# duck-v2.net
KiCad netlist of a schematic drawn in EAGLE
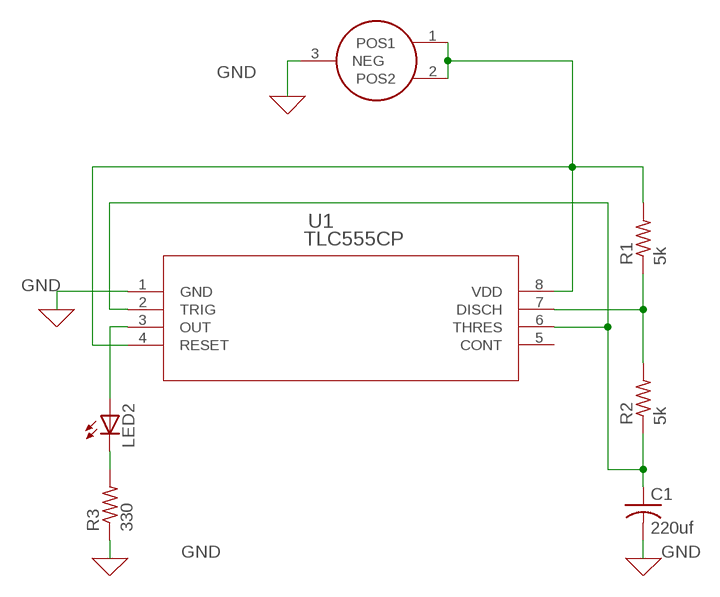
[diagram p0: schematic, sheet 1]

(export (version "E")
  (design (tool "Eeschema 10.0.6"))
  (components
    (comp (ref "C1")
      (value "220uf")
      (footprint "eagle-import:C025-024X044")
      (libsource (lib "eagle-import") (part "C-US025-024X044"))
    )
    (comp (ref "LED2")
      (value "LED5MM")
      (footprint "eagle-import:LED5MM")
      (libsource (lib "eagle-import") (part "LED5MM"))
    )
    (comp (ref "R1")
      (value "5k")
      (footprint "eagle-import:0204_7")
      (libsource (lib "eagle-import") (part "R-US_0204/7"))
    )
    (comp (ref "R2")
      (value "5k")
      (footprint "eagle-import:0204_7")
      (libsource (lib "eagle-import") (part "R-US_0204/7"))
    )
    (comp (ref "R3")
      (value "330")
      (footprint "eagle-import:0204_7")
      (libsource (lib "eagle-import") (part "R-US_0204/7"))
    )
    (comp (ref "U$1")
      (value "2895")
      (footprint "eagle-import:2895")
      (libsource (lib "eagle-import") (part "2895"))
    )
    (comp (ref "U1")
      (value "TLC555CP")
      (footprint "eagle-import:P8")
      (libsource (lib "eagle-import") (part "TLC555CP"))
    )
  )
  (nets
    (net (code "1") (name "GND") (class "Default")
      (node (ref "C1") (pin "2") (pinfunction "2_2") (pintype "passive"))
      (node (ref "R3") (pin "1") (pinfunction "1_1") (pintype "passive"))
      (node (ref "U$1") (pin "3") (pinfunction "NEG_3") (pintype "bidirectional"))
      (node (ref "U1") (pin "1") (pinfunction "GND_1") (pintype "power_in"))
    )
    (net (code "2") (name "Net-(LED2-C)") (class "Default")
      (node (ref "LED2") (pin "K") (pinfunction "C_K") (pintype "passive"))
      (node (ref "R3") (pin "2") (pinfunction "2_2") (pintype "passive"))
    )
    (net (code "3") (name "Net-(U$1-POS1)") (class "Default")
      (node (ref "R1") (pin "2") (pinfunction "2_2") (pintype "passive"))
      (node (ref "U$1") (pin "1") (pinfunction "POS1_1") (pintype "bidirectional"))
      (node (ref "U$1") (pin "2") (pinfunction "POS2_2") (pintype "bidirectional"))
      (node (ref "U1") (pin "4") (pinfunction "RESET_4") (pintype "input"))
      (node (ref "U1") (pin "8") (pinfunction "VDD_8") (pintype "power_in"))
    )
    (net (code "4") (name "Net-(U1-DISCH)") (class "Default")
      (node (ref "R1") (pin "1") (pinfunction "1_1") (pintype "passive"))
      (node (ref "R2") (pin "2") (pinfunction "2_2") (pintype "passive"))
      (node (ref "U1") (pin "7") (pinfunction "DISCH_7") (pintype "output"))
    )
    (net (code "5") (name "Net-(U1-OUT)") (class "Default")
      (node (ref "LED2") (pin "A") (pinfunction "A_A") (pintype "passive"))
      (node (ref "U1") (pin "3") (pinfunction "OUT_3") (pintype "output"))
    )
    (net (code "6") (name "Net-(U1-THRES)") (class "Default")
      (node (ref "C1") (pin "1") (pinfunction "1_1") (pintype "passive"))
      (node (ref "R2") (pin "1") (pinfunction "1_1") (pintype "passive"))
      (node (ref "U1") (pin "2") (pinfunction "TRIG_2") (pintype "input"))
      (node (ref "U1") (pin "6") (pinfunction "THRES_6") (pintype "input"))
    )
    (net (code "7") (name "unconnected-(U1-CONT-Pad5)") (class "Default")
      (node (ref "U1") (pin "5") (pinfunction "CONT_5") (pintype "input"))
    )
  )
)
